# GCC.net
KiCad netlist of a schematic drawn in Altium Designer
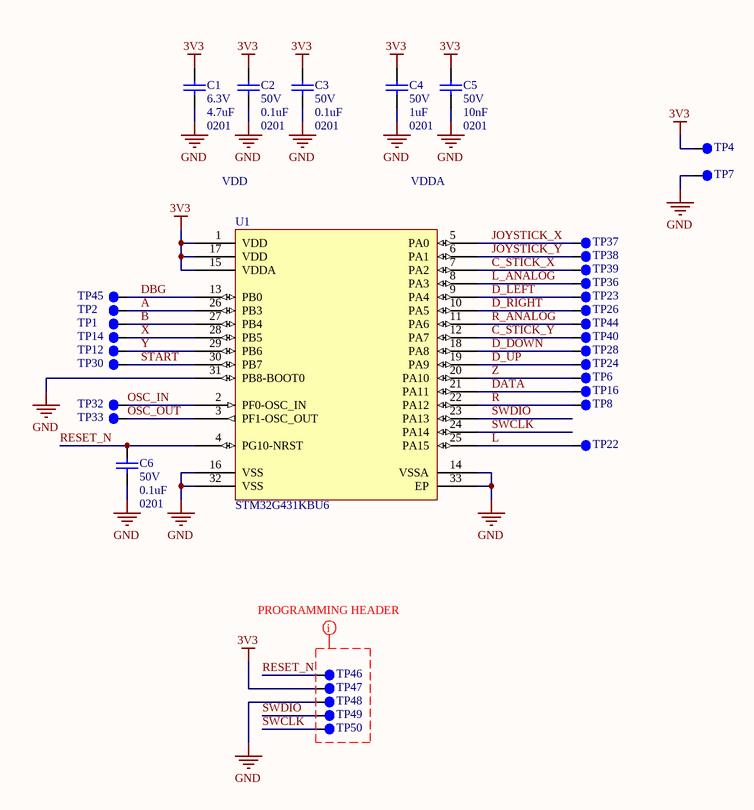
[diagram p0: GCC.SchDoc]

(export (version "E")
  (design (tool "Eeschema 10.0.6"))
  (components
    (comp (ref "C1")
      (value "4.7uF")
      (footprint "Footprint_Capacitor:CAPC0603X03N")
      (description "General purpose capacitor")
      (fields
        (field (name "RATED VOLTAGE") "6.3V")
        (field (name "PACKAGE") "0201")
        (field (name "Comment") "Capacitor")
      )
      (libsource (lib "Schematic_Generic") (part "Capacitor"))
    )
    (comp (ref "C2")
      (value "0.1uF")
      (footprint "Footprint_Capacitor:CAPC0603X03N")
      (description "General purpose capacitor")
      (fields
        (field (name "RATED VOLTAGE") "50V")
        (field (name "PACKAGE") "0201")
        (field (name "Comment") "Capacitor")
      )
      (libsource (lib "Schematic_Generic") (part "Capacitor"))
    )
    (comp (ref "C3")
      (value "0.1uF")
      (footprint "Footprint_Capacitor:CAPC0603X03N")
      (description "General purpose capacitor")
      (fields
        (field (name "RATED VOLTAGE") "50V")
        (field (name "PACKAGE") "0201")
        (field (name "Comment") "Capacitor")
      )
      (libsource (lib "Schematic_Generic") (part "Capacitor"))
    )
    (comp (ref "C4")
      (value "1uF")
      (footprint "Footprint_Capacitor:CAPC0603X03N")
      (description "General purpose capacitor")
      (fields
        (field (name "RATED VOLTAGE") "50V")
        (field (name "PACKAGE") "0201")
        (field (name "Comment") "Capacitor")
      )
      (libsource (lib "Schematic_Generic") (part "Capacitor"))
    )
    (comp (ref "C5")
      (value "10nF")
      (footprint "Footprint_Capacitor:CAPC0603X03N")
      (description "General purpose capacitor")
      (fields
        (field (name "RATED VOLTAGE") "50V")
        (field (name "PACKAGE") "0201")
        (field (name "Comment") "Capacitor")
      )
      (libsource (lib "Schematic_Generic") (part "Capacitor"))
    )
    (comp (ref "C6")
      (value "0.1uF")
      (footprint "Footprint_Capacitor:CAPC0603X03N")
      (description "General purpose capacitor")
      (fields
        (field (name "RATED VOLTAGE") "50V")
        (field (name "PACKAGE") "0201")
        (field (name "Comment") "Capacitor")
      )
      (libsource (lib "Schematic_Generic") (part "Capacitor"))
    )
    (comp (ref "TP1")
      (value "Test Point")
      (footprint "TP_RECTANGULAR_0.5X1MM_CAST")
      (description "General purpose test point")
      (libsource (lib "Schematic_Generic") (part "Test Point"))
    )
    (comp (ref "TP2")
      (value "Test Point")
      (footprint "TP_RECTANGULAR_0.5X1MM_CAST")
      (description "General purpose test point")
      (libsource (lib "Schematic_Generic") (part "Test Point"))
    )
    (comp (ref "TP4")
      (value "Test Point")
      (footprint "TP_RECTANGULAR_0.5X1MM_CAST")
      (description "General purpose test point")
      (libsource (lib "Schematic_Generic") (part "Test Point"))
    )
    (comp (ref "TP6")
      (value "Test Point")
      (footprint "TP_RECTANGULAR_0.5X1MM_CAST")
      (description "General purpose test point")
      (libsource (lib "Schematic_Generic") (part "Test Point"))
    )
    (comp (ref "TP7")
      (value "Test Point")
      (footprint "TP_RECTANGULAR_0.5X1MM_CAST")
      (description "General purpose test point")
      (libsource (lib "Schematic_Generic") (part "Test Point"))
    )
    (comp (ref "TP8")
      (value "Test Point")
      (footprint "TP_RECTANGULAR_0.5X1MM_CAST")
      (description "General purpose test point")
      (libsource (lib "Schematic_Generic") (part "Test Point"))
    )
    (comp (ref "TP12")
      (value "Test Point")
      (footprint "TP_RECTANGULAR_0.5X1MM_CAST")
      (description "General purpose test point")
      (libsource (lib "Schematic_Generic") (part "Test Point"))
    )
    (comp (ref "TP14")
      (value "Test Point")
      (footprint "TP_RECTANGULAR_0.5X1MM_CAST")
      (description "General purpose test point")
      (libsource (lib "Schematic_Generic") (part "Test Point"))
    )
    (comp (ref "TP16")
      (value "Test Point")
      (footprint "TP_RECTANGULAR_0.5X1MM_CAST")
      (description "General purpose test point")
      (libsource (lib "Schematic_Generic") (part "Test Point"))
    )
    (comp (ref "TP22")
      (value "Test Point")
      (footprint "TP_RECTANGULAR_0.5X1MM_CAST")
      (description "General purpose test point")
      (libsource (lib "Schematic_Generic") (part "Test Point"))
    )
    (comp (ref "TP23")
      (value "Test Point")
      (footprint "TP_RECTANGULAR_0.5X1MM_CAST")
      (description "General purpose test point")
      (libsource (lib "Schematic_Generic") (part "Test Point"))
    )
    (comp (ref "TP24")
      (value "Test Point")
      (footprint "TP_RECTANGULAR_0.5X1MM_CAST")
      (description "General purpose test point")
      (libsource (lib "Schematic_Generic") (part "Test Point"))
    )
    (comp (ref "TP26")
      (value "Test Point")
      (footprint "TP_RECTANGULAR_0.5X1MM_CAST")
      (description "General purpose test point")
      (libsource (lib "Schematic_Generic") (part "Test Point"))
    )
    (comp (ref "TP28")
      (value "Test Point")
      (footprint "TP_RECTANGULAR_0.5X1MM_CAST")
      (description "General purpose test point")
      (libsource (lib "Schematic_Generic") (part "Test Point"))
    )
    (comp (ref "TP30")
      (value "Test Point")
      (footprint "TP_RECTANGULAR_0.5X1MM_CAST")
      (description "General purpose test point")
      (libsource (lib "Schematic_Generic") (part "Test Point"))
    )
    (comp (ref "TP32")
      (value "Test Point")
      (footprint "TP_RECTANGULAR_0.5X1MM_CAST")
      (description "General purpose test point")
      (libsource (lib "Schematic_Generic") (part "Test Point"))
    )
    (comp (ref "TP33")
      (value "Test Point")
      (footprint "TP_RECTANGULAR_0.5X1MM_CAST")
      (description "General purpose test point")
      (libsource (lib "Schematic_Generic") (part "Test Point"))
    )
    (comp (ref "TP36")
      (value "Test Point")
      (footprint "TP_RECTANGULAR_0.5X1MM_CAST")
      (description "General purpose test point")
      (libsource (lib "Schematic_Generic") (part "Test Point"))
    )
    (comp (ref "TP37")
      (value "Test Point")
      (footprint "TP_RECTANGULAR_0.5X1MM_CAST")
      (description "General purpose test point")
      (libsource (lib "Schematic_Generic") (part "Test Point"))
    )
    (comp (ref "TP38")
      (value "Test Point")
      (footprint "TP_RECTANGULAR_0.5X1MM_CAST")
      (description "General purpose test point")
      (libsource (lib "Schematic_Generic") (part "Test Point"))
    )
    (comp (ref "TP39")
      (value "Test Point")
      (footprint "TP_RECTANGULAR_0.5X1MM_CAST")
      (description "General purpose test point")
      (libsource (lib "Schematic_Generic") (part "Test Point"))
    )
    (comp (ref "TP40")
      (value "Test Point")
      (footprint "TP_RECTANGULAR_0.5X1MM_CAST")
      (description "General purpose test point")
      (libsource (lib "Schematic_Generic") (part "Test Point"))
    )
    (comp (ref "TP44")
      (value "Test Point")
      (footprint "TP_RECTANGULAR_0.5X1MM_CAST")
      (description "General purpose test point")
      (libsource (lib "Schematic_Generic") (part "Test Point"))
    )
    (comp (ref "TP45")
      (value "Test Point")
      (footprint "TP_CIRCULAR_SMD_0.75MM")
      (description "General purpose test point")
      (libsource (lib "Schematic_Generic") (part "Test Point"))
    )
    (comp (ref "TP46")
      (value "Test Point")
      (footprint "TP_CIRCULAR_SMD_0.75MM")
      (description "General purpose test point")
      (libsource (lib "Schematic_Generic") (part "Test Point"))
    )
    (comp (ref "TP47")
      (value "Test Point")
      (footprint "TP_CIRCULAR_SMD_0.75MM")
      (description "General purpose test point")
      (libsource (lib "Schematic_Generic") (part "Test Point"))
    )
    (comp (ref "TP48")
      (value "Test Point")
      (footprint "TP_CIRCULAR_SMD_0.75MM")
      (description "General purpose test point")
      (libsource (lib "Schematic_Generic") (part "Test Point"))
    )
    (comp (ref "TP49")
      (value "Test Point")
      (footprint "TP_CIRCULAR_SMD_0.75MM")
      (description "General purpose test point")
      (libsource (lib "Schematic_Generic") (part "Test Point"))
    )
    (comp (ref "TP50")
      (value "Test Point")
      (footprint "TP_CIRCULAR_SMD_0.75MM")
      (description "General purpose test point")
      (libsource (lib "Schematic_Generic") (part "Test Point"))
    )
    (comp (ref "U1")
      (value "STM32G431KBU6")
      (footprint "Footprint_MCU:QFN50P500X500X60_HS-33N")
      (description "MCU 32-Bit ARM Cortex-M4 RISC 128KB Flash 1.71V to 3.6V 32-Pin UFQFPN")
      (fields (field (name "MANUFACTURER") "STMicroelectronics"))
      (libsource (lib "Schematic_MCU") (part "STM32G431KBU6"))
    )
  )
  (nets
    (net (code "1") (name "/A") (class "Default")
      (node (ref "TP2") (pin "1") (pintype "passive"))
      (node (ref "U1") (pin "26") (pinfunction "PB3_26") (pintype "bidirectional"))
    )
    (net (code "2") (name "/B") (class "Default")
      (node (ref "TP1") (pin "1") (pintype "passive"))
      (node (ref "U1") (pin "27") (pinfunction "PB4_27") (pintype "bidirectional"))
    )
    (net (code "3") (name "/C_STICK_X") (class "Default")
      (node (ref "TP39") (pin "1") (pintype "passive"))
      (node (ref "U1") (pin "7") (pinfunction "PA2_7") (pintype "bidirectional"))
    )
    (net (code "4") (name "/C_STICK_Y") (class "Default")
      (node (ref "TP40") (pin "1") (pintype "passive"))
      (node (ref "U1") (pin "12") (pinfunction "PA7_12") (pintype "bidirectional"))
    )
    (net (code "5") (name "/DATA") (class "Default")
      (node (ref "TP16") (pin "1") (pintype "passive"))
      (node (ref "U1") (pin "21") (pinfunction "PA11_21") (pintype "bidirectional"))
    )
    (net (code "6") (name "/DBG") (class "Default")
      (node (ref "TP45") (pin "1") (pintype "passive"))
      (node (ref "U1") (pin "13") (pinfunction "PB0_13") (pintype "bidirectional"))
    )
    (net (code "7") (name "/D_DOWN") (class "Default")
      (node (ref "TP28") (pin "1") (pintype "passive"))
      (node (ref "U1") (pin "18") (pinfunction "PA8_18") (pintype "bidirectional"))
    )
    (net (code "8") (name "/D_LEFT") (class "Default")
      (node (ref "TP23") (pin "1") (pintype "passive"))
      (node (ref "U1") (pin "9") (pinfunction "PA4_9") (pintype "bidirectional"))
    )
    (net (code "9") (name "/D_RIGHT") (class "Default")
      (node (ref "TP26") (pin "1") (pintype "passive"))
      (node (ref "U1") (pin "10") (pinfunction "PA5_10") (pintype "bidirectional"))
    )
    (net (code "10") (name "/D_UP") (class "Default")
      (node (ref "TP24") (pin "1") (pintype "passive"))
      (node (ref "U1") (pin "19") (pinfunction "PA9_19") (pintype "bidirectional"))
    )
    (net (code "11") (name "/JOYSTICK_X") (class "Default")
      (node (ref "TP37") (pin "1") (pintype "passive"))
      (node (ref "U1") (pin "5") (pinfunction "PA0_5") (pintype "bidirectional"))
    )
    (net (code "12") (name "/JOYSTICK_Y") (class "Default")
      (node (ref "TP38") (pin "1") (pintype "passive"))
      (node (ref "U1") (pin "6") (pinfunction "PA1_6") (pintype "bidirectional"))
    )
    (net (code "13") (name "/L") (class "Default")
      (node (ref "TP22") (pin "1") (pintype "passive"))
      (node (ref "U1") (pin "25") (pinfunction "PA15_25") (pintype "bidirectional"))
    )
    (net (code "14") (name "/L_ANALOG") (class "Default")
      (node (ref "TP36") (pin "1") (pintype "passive"))
      (node (ref "U1") (pin "8") (pinfunction "PA3_8") (pintype "bidirectional"))
    )
    (net (code "15") (name "/OSC_IN") (class "Default")
      (node (ref "TP32") (pin "1") (pintype "passive"))
      (node (ref "U1") (pin "2") (pinfunction "PF0-OSC_IN_2") (pintype "input"))
    )
    (net (code "16") (name "/OSC_OUT") (class "Default")
      (node (ref "TP33") (pin "1") (pintype "passive"))
      (node (ref "U1") (pin "3") (pinfunction "PF1-OSC_OUT_3") (pintype "output"))
    )
    (net (code "17") (name "/R") (class "Default")
      (node (ref "TP8") (pin "1") (pintype "passive"))
      (node (ref "U1") (pin "22") (pinfunction "PA12_22") (pintype "bidirectional"))
    )
    (net (code "18") (name "/RESET_N") (class "Default")
      (node (ref "C6") (pin "2") (pinfunction "2_2") (pintype "passive"))
      (node (ref "TP46") (pin "1") (pintype "passive"))
      (node (ref "U1") (pin "4") (pinfunction "PG10-NRST_4") (pintype "bidirectional"))
    )
    (net (code "19") (name "/R_ANALOG") (class "Default")
      (node (ref "TP44") (pin "1") (pintype "passive"))
      (node (ref "U1") (pin "11") (pinfunction "PA6_11") (pintype "bidirectional"))
    )
    (net (code "20") (name "/START") (class "Default")
      (node (ref "TP30") (pin "1") (pintype "passive"))
      (node (ref "U1") (pin "30") (pinfunction "PB7_30") (pintype "bidirectional"))
    )
    (net (code "21") (name "/SWCLK") (class "Default")
      (node (ref "TP50") (pin "1") (pintype "passive"))
      (node (ref "U1") (pin "24") (pinfunction "PA14_24") (pintype "bidirectional"))
    )
    (net (code "22") (name "/SWDIO") (class "Default")
      (node (ref "TP49") (pin "1") (pintype "passive"))
      (node (ref "U1") (pin "23") (pinfunction "PA13_23") (pintype "bidirectional"))
    )
    (net (code "23") (name "/X") (class "Default")
      (node (ref "TP14") (pin "1") (pintype "passive"))
      (node (ref "U1") (pin "28") (pinfunction "PB5_28") (pintype "bidirectional"))
    )
    (net (code "24") (name "/Y") (class "Default")
      (node (ref "TP12") (pin "1") (pintype "passive"))
      (node (ref "U1") (pin "29") (pinfunction "PB6_29") (pintype "bidirectional"))
    )
    (net (code "25") (name "/Z") (class "Default")
      (node (ref "TP6") (pin "1") (pintype "passive"))
      (node (ref "U1") (pin "20") (pinfunction "PA10_20") (pintype "bidirectional"))
    )
    (net (code "26") (name "3V3") (class "Default")
      (node (ref "C1") (pin "2") (pinfunction "2_2") (pintype "passive"))
      (node (ref "C2") (pin "2") (pinfunction "2_2") (pintype "passive"))
      (node (ref "C3") (pin "2") (pinfunction "2_2") (pintype "passive"))
      (node (ref "C4") (pin "2") (pinfunction "2_2") (pintype "passive"))
      (node (ref "C5") (pin "2") (pinfunction "2_2") (pintype "passive"))
      (node (ref "TP4") (pin "1") (pintype "passive"))
      (node (ref "TP47") (pin "1") (pintype "passive"))
      (node (ref "U1") (pin "1") (pinfunction "VDD_1") (pintype "power_in"))
      (node (ref "U1") (pin "15") (pinfunction "VDDA_15") (pintype "power_in"))
      (node (ref "U1") (pin "17") (pinfunction "VDD_17") (pintype "power_in"))
    )
    (net (code "27") (name "GND") (class "Default")
      (node (ref "C1") (pin "1") (pinfunction "1_1") (pintype "passive"))
      (node (ref "C2") (pin "1") (pinfunction "1_1") (pintype "passive"))
      (node (ref "C3") (pin "1") (pinfunction "1_1") (pintype "passive"))
      (node (ref "C4") (pin "1") (pinfunction "1_1") (pintype "passive"))
      (node (ref "C5") (pin "1") (pinfunction "1_1") (pintype "passive"))
      (node (ref "C6") (pin "1") (pinfunction "1_1") (pintype "passive"))
      (node (ref "TP48") (pin "1") (pintype "passive"))
      (node (ref "TP7") (pin "1") (pintype "passive"))
      (node (ref "U1") (pin "14") (pinfunction "VSSA_14") (pintype "power_in"))
      (node (ref "U1") (pin "16") (pinfunction "VSS_16") (pintype "power_in"))
      (node (ref "U1") (pin "31") (pinfunction "PB8-BOOT0_31") (pintype "bidirectional"))
      (node (ref "U1") (pin "32") (pinfunction "VSS_32") (pintype "power_in"))
      (node (ref "U1") (pin "33") (pinfunction "EP_33") (pintype "passive"))
    )
  )
)
